# FETs.net
KiCad netlist of a schematic drawn in Altium Designer
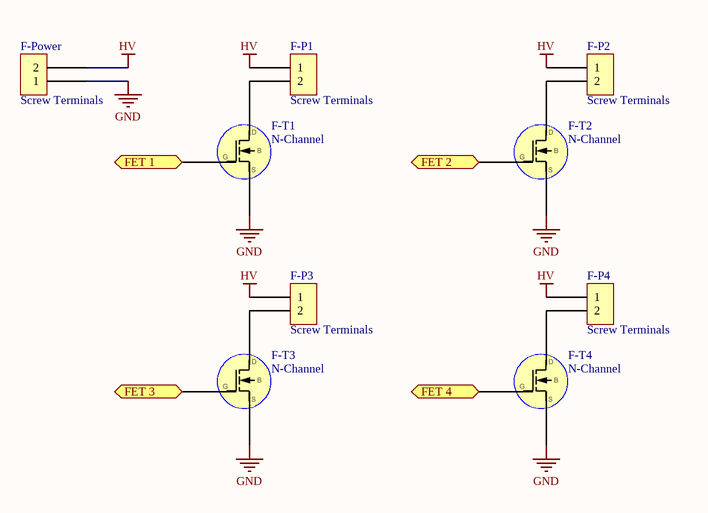
[diagram p0: FETs.SchDoc]

(export (version "E")
  (design (tool "Eeschema 10.0.6"))
  (components
    (comp (ref "F-P1")
      (value "Screw Terminals")
      (footprint "DG301-5.0-02")
      (libsource (lib "Headers") (part "Header 2x1"))
    )
    (comp (ref "F-P2")
      (value "Screw Terminals")
      (footprint "DG301-5.0-02")
      (libsource (lib "Headers") (part "Header 2x1"))
    )
    (comp (ref "F-P3")
      (value "Screw Terminals")
      (footprint "DG301-5.0-02")
      (libsource (lib "Headers") (part "Header 2x1"))
    )
    (comp (ref "F-P4")
      (value "Screw Terminals")
      (footprint "DG301-5.0-02")
      (libsource (lib "Headers") (part "Header 2x1"))
    )
    (comp (ref "F-Power")
      (value "Screw Terminals")
      (footprint "DG301-5.0-02")
      (libsource (lib "") (part "Header 2x1_1"))
    )
    (comp (ref "F-T1")
      (value "N-Channel")
      (footprint "TO-220 AB")
      (description "Enhancement Type")
      (libsource (lib "ICs") (part "FET N-Channel"))
    )
    (comp (ref "F-T2")
      (value "N-Channel")
      (footprint "TO-220 AB")
      (description "Enhancement Type")
      (libsource (lib "ICs") (part "FET N-Channel"))
    )
    (comp (ref "F-T3")
      (value "N-Channel")
      (footprint "TO-220 AB")
      (description "Enhancement Type")
      (libsource (lib "ICs") (part "FET N-Channel"))
    )
    (comp (ref "F-T4")
      (value "N-Channel")
      (footprint "TO-220 AB")
      (description "Enhancement Type")
      (libsource (lib "ICs") (part "FET N-Channel"))
    )
  )
  (nets
    (net (code "1") (name "/FET 1") (class "Default")
      (node (ref "F-T1") (pin "1") (pinfunction "1_1") (pintype "passive"))
    )
    (net (code "2") (name "/FET 2") (class "Default")
      (node (ref "F-T2") (pin "1") (pinfunction "1_1") (pintype "passive"))
    )
    (net (code "3") (name "/FET 3") (class "Default")
      (node (ref "F-T3") (pin "1") (pinfunction "1_1") (pintype "passive"))
    )
    (net (code "4") (name "/FET 4") (class "Default")
      (node (ref "F-T4") (pin "1") (pinfunction "1_1") (pintype "passive"))
    )
    (net (code "5") (name "GND") (class "Default")
      (node (ref "F-Power") (pin "1") (pinfunction "1_1") (pintype "passive"))
      (node (ref "F-T1") (pin "3") (pinfunction "3_3") (pintype "passive"))
      (node (ref "F-T2") (pin "3") (pinfunction "3_3") (pintype "passive"))
      (node (ref "F-T3") (pin "3") (pinfunction "3_3") (pintype "passive"))
      (node (ref "F-T4") (pin "3") (pinfunction "3_3") (pintype "passive"))
    )
    (net (code "6") (name "HV") (class "Default")
      (node (ref "F-P1") (pin "1") (pinfunction "1_1") (pintype "passive"))
      (node (ref "F-P2") (pin "1") (pinfunction "1_1") (pintype "passive"))
      (node (ref "F-P3") (pin "1") (pinfunction "1_1") (pintype "passive"))
      (node (ref "F-P4") (pin "1") (pinfunction "1_1") (pintype "passive"))
      (node (ref "F-Power") (pin "2") (pinfunction "2_2") (pintype "passive"))
    )
    (net (code "7") (name "Net-(F-P1-Pad2)") (class "Default")
      (node (ref "F-P1") (pin "2") (pinfunction "2_2") (pintype "passive"))
      (node (ref "F-T1") (pin "2") (pinfunction "2_2") (pintype "passive"))
    )
    (net (code "8") (name "Net-(F-P2-Pad2)") (class "Default")
      (node (ref "F-P2") (pin "2") (pinfunction "2_2") (pintype "passive"))
      (node (ref "F-T2") (pin "2") (pinfunction "2_2") (pintype "passive"))
    )
    (net (code "9") (name "Net-(F-P3-Pad2)") (class "Default")
      (node (ref "F-P3") (pin "2") (pinfunction "2_2") (pintype "passive"))
      (node (ref "F-T3") (pin "2") (pinfunction "2_2") (pintype "passive"))
    )
    (net (code "10") (name "Net-(F-P4-Pad2)") (class "Default")
      (node (ref "F-P4") (pin "2") (pinfunction "2_2") (pintype "passive"))
      (node (ref "F-T4") (pin "2") (pinfunction "2_2") (pintype "passive"))
    )
  )
)
